# Model_64_Sequencer_Cartridge_v1.net
KiCad netlist of a schematic drawn in EAGLE
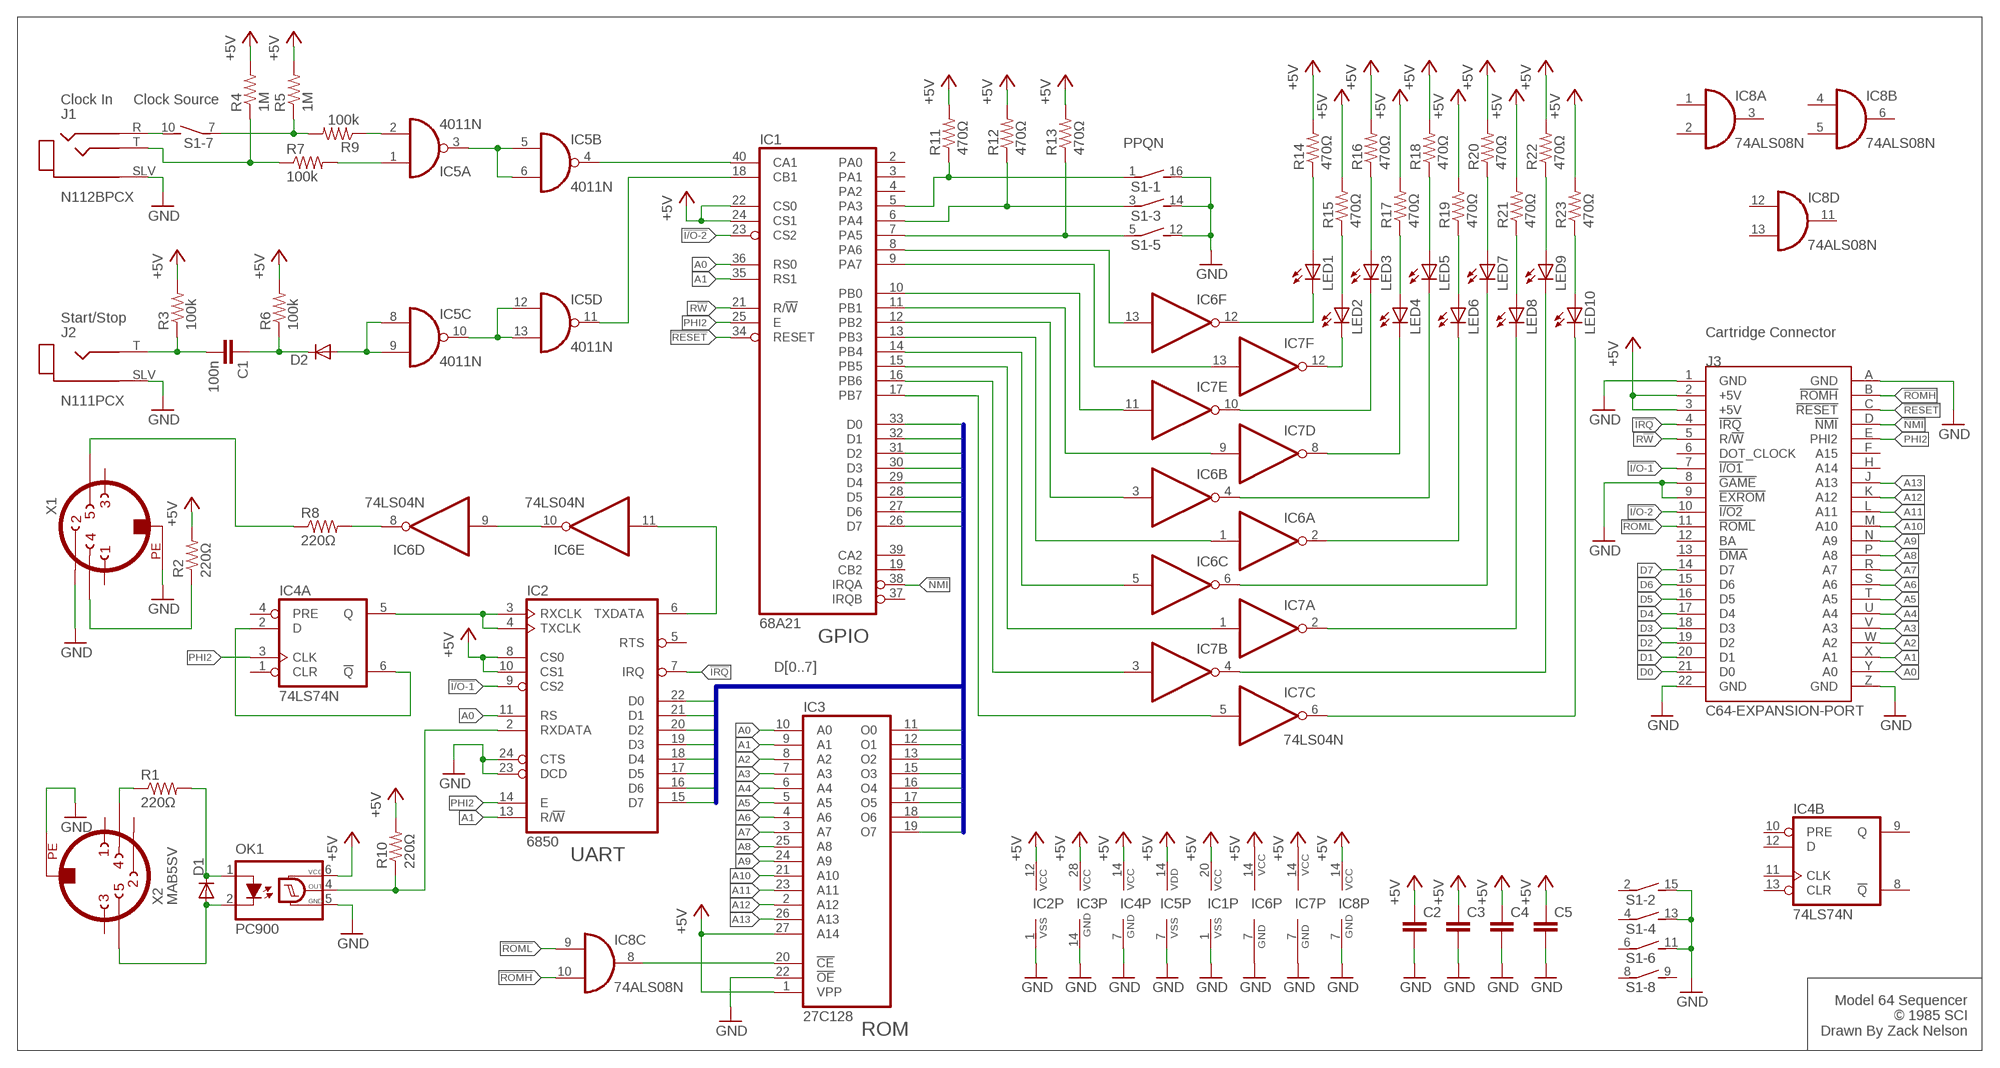
[diagram p0: schematic, sheet 1]

(export (version "E")
  (design (tool "Eeschema 10.0.6"))
  (components
    (comp (ref "C1")
      (value "100n")
      (footprint "eagle-import:C050-024X044")
      (libsource (lib "eagle-import") (part "C-EU050-024X044"))
    )
    (comp (ref "C2")
      (value "C-EU050-024X044")
      (footprint "eagle-import:C050-024X044")
      (libsource (lib "eagle-import") (part "C-EU050-024X044"))
    )
    (comp (ref "C3")
      (value "C-EU050-024X044")
      (footprint "eagle-import:C050-024X044")
      (libsource (lib "eagle-import") (part "C-EU050-024X044"))
    )
    (comp (ref "C4")
      (value "C-EU050-024X044")
      (footprint "eagle-import:C050-024X044")
      (libsource (lib "eagle-import") (part "C-EU050-024X044"))
    )
    (comp (ref "C5")
      (value "C-EU050-024X044")
      (footprint "eagle-import:C050-024X044")
      (libsource (lib "eagle-import") (part "C-EU050-024X044"))
    )
    (comp (ref "D1")
      (value "DIODE-D-7.5")
      (footprint "eagle-import:D-7.5")
      (libsource (lib "eagle-import") (part "DIODE-D-7.5"))
    )
    (comp (ref "D2")
      (value "DIODE-D-7.5")
      (footprint "eagle-import:D-7.5")
      (libsource (lib "eagle-import") (part "DIODE-D-7.5"))
    )
    (comp (ref "IC1")
      (value "68A21")
      (footprint "eagle-import:DIL40")
      (fields (field (name "MF") "NTE ELECTRONICS") (field (name "MPN") "NTE6821"))
      (libsource (lib "eagle-import") (part "6821"))
    )
    (comp (ref "IC2")
      (value "6850")
      (footprint "eagle-import:DIL24")
      (fields (field (name "MF") "NTE ELECTRONICS") (field (name "MPN") "NTE6850"))
      (libsource (lib "eagle-import") (part "6850"))
    )
    (comp (ref "IC3")
      (value "27C128")
      (footprint "eagle-import:DIL28")
      (libsource (lib "eagle-import") (part "27256"))
    )
    (comp (ref "IC4")
      (value "74LS74N")
      (footprint "eagle-import:DIL14")
      (libsource (lib "eagle-import") (part "7474NLS"))
    )
    (comp (ref "IC5")
      (value "4011N")
      (footprint "eagle-import:DIL14")
      (libsource (lib "eagle-import") (part "4011N"))
    )
    (comp (ref "IC6")
      (value "74LS04N")
      (footprint "eagle-import:DIL14")
      (libsource (lib "eagle-import") (part "7404NLS"))
    )
    (comp (ref "IC7")
      (value "74LS04N")
      (footprint "eagle-import:DIL14")
      (libsource (lib "eagle-import") (part "7404NLS"))
    )
    (comp (ref "IC8")
      (value "74ALS08N")
      (footprint "eagle-import:DIL14")
      (libsource (lib "eagle-import") (part "7408NALS"))
    )
    (comp (ref "J1")
      (value "N112BPCX")
      (footprint "eagle-import:SWITCHCRAFT_N112BPCX")
      (fields (field (name "MANUFACTURER") "Switchcarft"))
      (libsource (lib "eagle-import") (part "N112BPCX"))
    )
    (comp (ref "J2")
      (value "N111PCX")
      (footprint "eagle-import:SWITCHCRAFT_N111PCX")
      (fields (field (name "MANUFACTURER") "Switchcarft"))
      (libsource (lib "eagle-import") (part "N111PCX"))
    )
    (comp (ref "J3")
      (value "C64-EXPANSION-PORT")
      (footprint "eagle-import:EXPANSIO_SQ")
      (libsource (lib "eagle-import") (part "C64-EXPANSIONPNARROW"))
    )
    (comp (ref "LED1")
      (value "LED3MM")
      (footprint "eagle-import:LED3MM")
      (libsource (lib "eagle-import") (part "LED3MM"))
    )
    (comp (ref "LED2")
      (value "LED3MM")
      (footprint "eagle-import:LED3MM")
      (libsource (lib "eagle-import") (part "LED3MM"))
    )
    (comp (ref "LED3")
      (value "LED3MM")
      (footprint "eagle-import:LED3MM")
      (libsource (lib "eagle-import") (part "LED3MM"))
    )
    (comp (ref "LED4")
      (value "LED3MM")
      (footprint "eagle-import:LED3MM")
      (libsource (lib "eagle-import") (part "LED3MM"))
    )
    (comp (ref "LED5")
      (value "LED3MM")
      (footprint "eagle-import:LED3MM")
      (libsource (lib "eagle-import") (part "LED3MM"))
    )
    (comp (ref "LED6")
      (value "LED3MM")
      (footprint "eagle-import:LED3MM")
      (libsource (lib "eagle-import") (part "LED3MM"))
    )
    (comp (ref "LED7")
      (value "LED3MM")
      (footprint "eagle-import:LED3MM")
      (libsource (lib "eagle-import") (part "LED3MM"))
    )
    (comp (ref "LED8")
      (value "LED3MM")
      (footprint "eagle-import:LED3MM")
      (libsource (lib "eagle-import") (part "LED3MM"))
    )
    (comp (ref "LED9")
      (value "LED3MM")
      (footprint "eagle-import:LED3MM")
      (libsource (lib "eagle-import") (part "LED3MM"))
    )
    (comp (ref "LED10")
      (value "LED3MM")
      (footprint "eagle-import:LED3MM")
      (libsource (lib "eagle-import") (part "LED3MM"))
    )
    (comp (ref "OK1")
      (value "PC900")
      (footprint "eagle-import:DIL06")
      (fields (field (name "MF") "FAIRCHILD SEMICONDUCTOR") (field (name "MPN") "H11L1-M"))
      (libsource (lib "eagle-import") (part "H11LM1"))
    )
    (comp (ref "R1")
      (value "220Ω")
      (footprint "eagle-import:0207_12")
      (libsource (lib "eagle-import") (part "R-US_0207/12"))
    )
    (comp (ref "R2")
      (value "220Ω")
      (footprint "eagle-import:0207_12")
      (libsource (lib "eagle-import") (part "R-US_0207/12"))
    )
    (comp (ref "R3")
      (value "100k")
      (footprint "eagle-import:0207_12")
      (libsource (lib "eagle-import") (part "R-US_0207/12"))
    )
    (comp (ref "R4")
      (value "1M")
      (footprint "eagle-import:0207_12")
      (libsource (lib "eagle-import") (part "R-US_0207/12"))
    )
    (comp (ref "R5")
      (value "1M")
      (footprint "eagle-import:0207_12")
      (libsource (lib "eagle-import") (part "R-US_0207/12"))
    )
    (comp (ref "R6")
      (value "100k")
      (footprint "eagle-import:0207_12")
      (libsource (lib "eagle-import") (part "R-US_0207/12"))
    )
    (comp (ref "R7")
      (value "100k")
      (footprint "eagle-import:0207_12")
      (libsource (lib "eagle-import") (part "R-US_0207/12"))
    )
    (comp (ref "R8")
      (value "220Ω")
      (footprint "eagle-import:0207_12")
      (libsource (lib "eagle-import") (part "R-US_0207/12"))
    )
    (comp (ref "R9")
      (value "100k")
      (footprint "eagle-import:0207_12")
      (libsource (lib "eagle-import") (part "R-US_0207/12"))
    )
    (comp (ref "R10")
      (value "220Ω")
      (footprint "eagle-import:0207_12")
      (libsource (lib "eagle-import") (part "R-US_0207/12"))
    )
    (comp (ref "R11")
      (value "470Ω")
      (footprint "eagle-import:0207_12")
      (libsource (lib "eagle-import") (part "R-US_0207/12"))
    )
    (comp (ref "R12")
      (value "470Ω")
      (footprint "eagle-import:0207_12")
      (libsource (lib "eagle-import") (part "R-US_0207/12"))
    )
    (comp (ref "R13")
      (value "470Ω")
      (footprint "eagle-import:0207_12")
      (libsource (lib "eagle-import") (part "R-US_0207/12"))
    )
    (comp (ref "R14")
      (value "470Ω")
      (footprint "eagle-import:0207_12")
      (libsource (lib "eagle-import") (part "R-US_0207/12"))
    )
    (comp (ref "R15")
      (value "470Ω")
      (footprint "eagle-import:0207_12")
      (libsource (lib "eagle-import") (part "R-US_0207/12"))
    )
    (comp (ref "R16")
      (value "470Ω")
      (footprint "eagle-import:0207_12")
      (libsource (lib "eagle-import") (part "R-US_0207/12"))
    )
    (comp (ref "R17")
      (value "470Ω")
      (footprint "eagle-import:0207_12")
      (libsource (lib "eagle-import") (part "R-US_0207/12"))
    )
    (comp (ref "R18")
      (value "470Ω")
      (footprint "eagle-import:0207_12")
      (libsource (lib "eagle-import") (part "R-US_0207/12"))
    )
    (comp (ref "R19")
      (value "470Ω")
      (footprint "eagle-import:0207_12")
      (libsource (lib "eagle-import") (part "R-US_0207/12"))
    )
    (comp (ref "R20")
      (value "470Ω")
      (footprint "eagle-import:0207_12")
      (libsource (lib "eagle-import") (part "R-US_0207/12"))
    )
    (comp (ref "R21")
      (value "470Ω")
      (footprint "eagle-import:0207_12")
      (libsource (lib "eagle-import") (part "R-US_0207/12"))
    )
    (comp (ref "R22")
      (value "470Ω")
      (footprint "eagle-import:0207_12")
      (libsource (lib "eagle-import") (part "R-US_0207/12"))
    )
    (comp (ref "R23")
      (value "470Ω")
      (footprint "eagle-import:0207_12")
      (libsource (lib "eagle-import") (part "R-US_0207/12"))
    )
    (comp (ref "S1")
      (value "DIP08S")
      (footprint "eagle-import:DIP08S")
      (libsource (lib "eagle-import") (part "DIP08S"))
    )
    (comp (ref "X1")
      (value "MAB5SV")
      (footprint "eagle-import:MAB5SV")
      (libsource (lib "eagle-import") (part "MAB5SV"))
    )
    (comp (ref "X2")
      (value "MAB5SV")
      (footprint "eagle-import:MAB5SV")
      (libsource (lib "eagle-import") (part "MAB5SV"))
    )
  )
  (nets
    (net (code "1") (name "+5V") (class "Default")
      (node (ref "C2") (pin "1") (pinfunction "1_1") (pintype "passive"))
      (node (ref "C3") (pin "1") (pinfunction "1_1") (pintype "passive"))
      (node (ref "C4") (pin "1") (pinfunction "1_1") (pintype "passive"))
      (node (ref "C5") (pin "1") (pinfunction "1_1") (pintype "passive"))
      (node (ref "IC1") (pin "20") (pinfunction "VCC_20") (pintype "power_in"))
      (node (ref "IC1") (pin "22") (pinfunction "CS0_22") (pintype "input"))
      (node (ref "IC1") (pin "24") (pinfunction "CS1_24") (pintype "input"))
      (node (ref "IC2") (pin "10") (pinfunction "CS1_10") (pintype "input"))
      (node (ref "IC2") (pin "12") (pinfunction "VCC_12") (pintype "power_in"))
      (node (ref "IC2") (pin "8") (pinfunction "CS0_8") (pintype "input"))
      (node (ref "IC3") (pin "1") (pinfunction "VPP_1") (pintype "input"))
      (node (ref "IC3") (pin "27") (pinfunction "A14_27") (pintype "input"))
      (node (ref "IC3") (pin "28") (pinfunction "VCC_28") (pintype "power_in"))
      (node (ref "IC4") (pin "14") (pinfunction "VCC_14") (pintype "power_in"))
      (node (ref "IC5") (pin "14") (pinfunction "VDD_14") (pintype "power_in"))
      (node (ref "IC6") (pin "14") (pinfunction "VCC_14") (pintype "power_in"))
      (node (ref "IC7") (pin "14") (pinfunction "VCC_14") (pintype "power_in"))
      (node (ref "IC8") (pin "14") (pinfunction "VCC_14") (pintype "power_in"))
      (node (ref "J3") (pin "2") (pinfunction "+5V_2") (pintype "power_in"))
      (node (ref "J3") (pin "3") (pinfunction "+5V_3") (pintype "power_in"))
      (node (ref "OK1") (pin "6") (pinfunction "VCC_6") (pintype "power_in"))
      (node (ref "R10") (pin "2") (pinfunction "2_2") (pintype "passive"))
      (node (ref "R11") (pin "2") (pinfunction "2_2") (pintype "passive"))
      (node (ref "R12") (pin "2") (pinfunction "2_2") (pintype "passive"))
      (node (ref "R13") (pin "2") (pinfunction "2_2") (pintype "passive"))
      (node (ref "R14") (pin "2") (pinfunction "2_2") (pintype "passive"))
      (node (ref "R15") (pin "2") (pinfunction "2_2") (pintype "passive"))
      (node (ref "R16") (pin "2") (pinfunction "2_2") (pintype "passive"))
      (node (ref "R17") (pin "2") (pinfunction "2_2") (pintype "passive"))
      (node (ref "R18") (pin "2") (pinfunction "2_2") (pintype "passive"))
      (node (ref "R19") (pin "2") (pinfunction "2_2") (pintype "passive"))
      (node (ref "R2") (pin "2") (pinfunction "2_2") (pintype "passive"))
      (node (ref "R20") (pin "2") (pinfunction "2_2") (pintype "passive"))
      (node (ref "R21") (pin "2") (pinfunction "2_2") (pintype "passive"))
      (node (ref "R22") (pin "2") (pinfunction "2_2") (pintype "passive"))
      (node (ref "R23") (pin "2") (pinfunction "2_2") (pintype "passive"))
      (node (ref "R3") (pin "2") (pinfunction "2_2") (pintype "passive"))
      (node (ref "R4") (pin "2") (pinfunction "2_2") (pintype "passive"))
      (node (ref "R5") (pin "2") (pinfunction "2_2") (pintype "passive"))
      (node (ref "R6") (pin "2") (pinfunction "2_2") (pintype "passive"))
    )
    (net (code "3") (name "/R~{W}") (class "Default")
      (node (ref "IC1") (pin "21") (pinfunction "R/~{W}_21") (pintype "input"))
      (node (ref "J3") (pin "5") (pinfunction "R/~{W}_5") (pintype "output"))
    )
    (net (code "4") (name "/~{IRQ}") (class "Default")
      (node (ref "IC2") (pin "7") (pinfunction "IRQ_7") (pintype "output"))
      (node (ref "J3") (pin "4") (pinfunction "~{IRQ}_4") (pintype "input"))
    )
    (net (code "5") (name "/~{I{slash}O-1}") (class "Default")
      (node (ref "IC2") (pin "9") (pinfunction "CS2_9") (pintype "input"))
      (node (ref "J3") (pin "7") (pinfunction "~{I/O1}_7") (pintype "output"))
    )
    (net (code "6") (name "/~{I{slash}O-2}") (class "Default")
      (node (ref "IC1") (pin "23") (pinfunction "CS2_23") (pintype "input"))
      (node (ref "J3") (pin "10") (pinfunction "~{I/O2}_10") (pintype "output"))
    )
    (net (code "7") (name "/~{NMI}") (class "Default")
      (node (ref "IC1") (pin "38") (pinfunction "IRQA_38") (pintype "open_collector"))
      (node (ref "J3") (pin "D") (pinfunction "~{NMI}_D") (pintype "input"))
    )
    (net (code "8") (name "/~{RESET}") (class "Default")
      (node (ref "IC1") (pin "34") (pinfunction "RESET_34") (pintype "input"))
      (node (ref "J3") (pin "C") (pinfunction "~{RESET}_C") (pintype "open_collector"))
    )
    (net (code "9") (name "/~{ROMH}") (class "Default")
      (node (ref "IC8") (pin "10") (pinfunction "I1_10") (pintype "input"))
      (node (ref "J3") (pin "B") (pinfunction "~{ROMH}_B") (pintype "output"))
    )
    (net (code "10") (name "/~{ROML}") (class "Default")
      (node (ref "IC8") (pin "9") (pinfunction "I0_9") (pintype "input"))
      (node (ref "J3") (pin "11") (pinfunction "~{ROML}_11") (pintype "output"))
    )
    (net (code "11") (name "A0") (class "Default")
      (node (ref "IC1") (pin "36") (pinfunction "RS0_36") (pintype "input"))
      (node (ref "IC2") (pin "11") (pinfunction "RS_11") (pintype "input"))
      (node (ref "IC3") (pin "10") (pinfunction "A0_10") (pintype "input"))
      (node (ref "J3") (pin "Y") (pinfunction "A0_Y") (pintype "bidirectional"))
    )
    (net (code "12") (name "A1") (class "Default")
      (node (ref "IC1") (pin "35") (pinfunction "RS1_35") (pintype "input"))
      (node (ref "IC2") (pin "13") (pinfunction "R/~{W}_13") (pintype "input"))
      (node (ref "IC3") (pin "9") (pinfunction "A1_9") (pintype "input"))
      (node (ref "J3") (pin "X") (pinfunction "A1_X") (pintype "bidirectional"))
    )
    (net (code "13") (name "A2") (class "Default")
      (node (ref "IC3") (pin "8") (pinfunction "A2_8") (pintype "input"))
      (node (ref "J3") (pin "W") (pinfunction "A2_W") (pintype "bidirectional"))
    )
    (net (code "14") (name "A3") (class "Default")
      (node (ref "IC3") (pin "7") (pinfunction "A3_7") (pintype "input"))
      (node (ref "J3") (pin "V") (pinfunction "A3_V") (pintype "bidirectional"))
    )
    (net (code "15") (name "A4") (class "Default")
      (node (ref "IC3") (pin "6") (pinfunction "A4_6") (pintype "input"))
      (node (ref "J3") (pin "U") (pinfunction "A4_U") (pintype "bidirectional"))
    )
    (net (code "16") (name "A5") (class "Default")
      (node (ref "IC3") (pin "5") (pinfunction "A5_5") (pintype "input"))
      (node (ref "J3") (pin "T") (pinfunction "A5_T") (pintype "bidirectional"))
    )
    (net (code "17") (name "A6") (class "Default")
      (node (ref "IC3") (pin "4") (pinfunction "A6_4") (pintype "input"))
      (node (ref "J3") (pin "S") (pinfunction "A6_S") (pintype "bidirectional"))
    )
    (net (code "18") (name "A7") (class "Default")
      (node (ref "IC3") (pin "3") (pinfunction "A7_3") (pintype "input"))
      (node (ref "J3") (pin "R") (pinfunction "A7_R") (pintype "bidirectional"))
    )
    (net (code "19") (name "A8") (class "Default")
      (node (ref "IC3") (pin "25") (pinfunction "A8_25") (pintype "input"))
      (node (ref "J3") (pin "P") (pinfunction "A8_P") (pintype "bidirectional"))
    )
    (net (code "20") (name "A9") (class "Default")
      (node (ref "IC3") (pin "24") (pinfunction "A9_24") (pintype "input"))
      (node (ref "J3") (pin "N") (pinfunction "A9_N") (pintype "bidirectional"))
    )
    (net (code "21") (name "A10") (class "Default")
      (node (ref "IC3") (pin "21") (pinfunction "A10_21") (pintype "input"))
      (node (ref "J3") (pin "M") (pinfunction "A10_M") (pintype "bidirectional"))
    )
    (net (code "22") (name "A11") (class "Default")
      (node (ref "IC3") (pin "23") (pinfunction "A11_23") (pintype "input"))
      (node (ref "J3") (pin "L") (pinfunction "A11_L") (pintype "bidirectional"))
    )
    (net (code "23") (name "A12") (class "Default")
      (node (ref "IC3") (pin "2") (pinfunction "A12_2") (pintype "input"))
      (node (ref "J3") (pin "K") (pinfunction "A12_K") (pintype "bidirectional"))
    )
    (net (code "24") (name "A13") (class "Default")
      (node (ref "IC3") (pin "26") (pinfunction "A13_26") (pintype "input"))
      (node (ref "J3") (pin "J") (pinfunction "A13_J") (pintype "bidirectional"))
    )
    (net (code "25") (name "D0") (class "Default")
      (node (ref "IC1") (pin "33") (pinfunction "D0_33") (pintype "bidirectional"))
      (node (ref "IC2") (pin "22") (pinfunction "D0_22") (pintype "bidirectional"))
      (node (ref "IC3") (pin "11") (pinfunction "O0_11") (pintype "tri_state"))
      (node (ref "J3") (pin "21") (pinfunction "D0_21") (pintype "bidirectional"))
    )
    (net (code "26") (name "D1") (class "Default")
      (node (ref "IC1") (pin "32") (pinfunction "D1_32") (pintype "bidirectional"))
      (node (ref "IC2") (pin "21") (pinfunction "D1_21") (pintype "bidirectional"))
      (node (ref "IC3") (pin "12") (pinfunction "O1_12") (pintype "tri_state"))
      (node (ref "J3") (pin "20") (pinfunction "D1_20") (pintype "bidirectional"))
    )
    (net (code "27") (name "D2") (class "Default")
      (node (ref "IC1") (pin "31") (pinfunction "D2_31") (pintype "bidirectional"))
      (node (ref "IC2") (pin "20") (pinfunction "D2_20") (pintype "bidirectional"))
      (node (ref "IC3") (pin "13") (pinfunction "O2_13") (pintype "tri_state"))
      (node (ref "J3") (pin "19") (pinfunction "D2_19") (pintype "bidirectional"))
    )
    (net (code "28") (name "D3") (class "Default")
      (node (ref "IC1") (pin "30") (pinfunction "D3_30") (pintype "bidirectional"))
      (node (ref "IC2") (pin "19") (pinfunction "D3_19") (pintype "bidirectional"))
      (node (ref "IC3") (pin "15") (pinfunction "O3_15") (pintype "tri_state"))
      (node (ref "J3") (pin "18") (pinfunction "D3_18") (pintype "bidirectional"))
    )
    (net (code "29") (name "D4") (class "Default")
      (node (ref "IC1") (pin "29") (pinfunction "D4_29") (pintype "bidirectional"))
      (node (ref "IC2") (pin "18") (pinfunction "D4_18") (pintype "bidirectional"))
      (node (ref "IC3") (pin "16") (pinfunction "O4_16") (pintype "tri_state"))
      (node (ref "J3") (pin "17") (pinfunction "D4_17") (pintype "bidirectional"))
    )
    (net (code "30") (name "D5") (class "Default")
      (node (ref "IC1") (pin "28") (pinfunction "D5_28") (pintype "bidirectional"))
      (node (ref "IC2") (pin "17") (pinfunction "D5_17") (pintype "bidirectional"))
      (node (ref "IC3") (pin "17") (pinfunction "O5_17") (pintype "tri_state"))
      (node (ref "J3") (pin "16") (pinfunction "D5_16") (pintype "bidirectional"))
    )
    (net (code "31") (name "D6") (class "Default")
      (node (ref "IC1") (pin "27") (pinfunction "D6_27") (pintype "bidirectional"))
      (node (ref "IC2") (pin "16") (pinfunction "D6_16") (pintype "bidirectional"))
      (node (ref "IC3") (pin "18") (pinfunction "O6_18") (pintype "tri_state"))
      (node (ref "J3") (pin "15") (pinfunction "D6_15") (pintype "bidirectional"))
    )
    (net (code "32") (name "D7") (class "Default")
      (node (ref "IC1") (pin "26") (pinfunction "D7_26") (pintype "bidirectional"))
      (node (ref "IC2") (pin "15") (pinfunction "D7_15") (pintype "bidirectional"))
      (node (ref "IC3") (pin "19") (pinfunction "O7_19") (pintype "tri_state"))
      (node (ref "J3") (pin "14") (pinfunction "D7_14") (pintype "bidirectional"))
    )
    (net (code "33") (name "GND") (class "Default")
      (node (ref "C2") (pin "2") (pinfunction "2_2") (pintype "passive"))
      (node (ref "C3") (pin "2") (pinfunction "2_2") (pintype "passive"))
      (node (ref "C4") (pin "2") (pinfunction "2_2") (pintype "passive"))
      (node (ref "C5") (pin "2") (pinfunction "2_2") (pintype "passive"))
      (node (ref "IC1") (pin "1") (pinfunction "VSS_1") (pintype "power_in"))
      (node (ref "IC2") (pin "1") (pinfunction "VSS_1") (pintype "power_in"))
      (node (ref "IC2") (pin "23") (pinfunction "DCD_23") (pintype "input"))
      (node (ref "IC2") (pin "24") (pinfunction "CTS_24") (pintype "input"))
      (node (ref "IC3") (pin "14") (pinfunction "GND_14") (pintype "power_in"))
      (node (ref "IC3") (pin "22") (pinfunction "~{OE}_22") (pintype "input"))
      (node (ref "IC4") (pin "7") (pinfunction "GND_7") (pintype "power_in"))
      (node (ref "IC5") (pin "7") (pinfunction "VSS_7") (pintype "power_in"))
      (node (ref "IC6") (pin "7") (pinfunction "GND_7") (pintype "power_in"))
      (node (ref "IC7") (pin "7") (pinfunction "GND_7") (pintype "power_in"))
      (node (ref "IC8") (pin "7") (pinfunction "GND_7") (pintype "power_in"))
      (node (ref "J1") (pin "SLV") (pinfunction "SLEEVE_SLV") (pintype "passive"))
      (node (ref "J2") (pin "SLV") (pinfunction "SLEEVE_SLV") (pintype "passive"))
      (node (ref "J3") (pin "1") (pinfunction "GND_1") (pintype "power_in"))
      (node (ref "J3") (pin "22") (pinfunction "GND_22") (pintype "power_in"))
      (node (ref "J3") (pin "8") (pinfunction "~{GAME}_8") (pintype "input"))
      (node (ref "J3") (pin "9") (pinfunction "~{EXROM}_9") (pintype "input"))
      (node (ref "J3") (pin "A") (pinfunction "GND_A") (pintype "power_in"))
      (node (ref "J3") (pin "Z") (pinfunction "GND_Z") (pintype "power_in"))
      (node (ref "OK1") (pin "5") (pinfunction "GND_5") (pintype "power_in"))
      (node (ref "S1") (pin "11") (pinfunction "2_11") (pintype "passive"))
      (node (ref "S1") (pin "12") (pinfunction "2_12") (pintype "passive"))
      (node (ref "S1") (pin "13") (pinfunction "2_13") (pintype "passive"))
      (node (ref "S1") (pin "14") (pinfunction "2_14") (pintype "passive"))
      (node (ref "S1") (pin "15") (pinfunction "2_15") (pintype "passive"))
      (node (ref "S1") (pin "16") (pinfunction "2_16") (pintype "passive"))
      (node (ref "X1") (pin "2") (pinfunction "2_2") (pintype "passive"))
      (node (ref "X1") (pin "PE") (pinfunction "PE_PE") (pintype "power_in"))
      (node (ref "X2") (pin "PE") (pinfunction "PE_PE") (pintype "power_in"))
    )
    (net (code "34") (name "Net-(C1-Pad1)") (class "Default")
      (node (ref "C1") (pin "1") (pinfunction "1_1") (pintype "passive"))
      (node (ref "D2") (pin "C") (pinfunction "C_C") (pintype "passive"))
      (node (ref "R6") (pin "1") (pinfunction "1_1") (pintype "passive"))
    )
    (net (code "35") (name "Net-(IC1A-CA1)") (class "Default")
      (node (ref "IC1") (pin "40") (pinfunction "CA1_40") (pintype "input"))
      (node (ref "IC5") (pin "4") (pinfunction "O_4") (pintype "output"))
    )
    (net (code "36") (name "Net-(IC1A-CB1)") (class "Default")
      (node (ref "IC1") (pin "18") (pinfunction "CB1_18") (pintype "input"))
      (node (ref "IC5") (pin "11") (pinfunction "O_11") (pintype "output"))
    )
    (net (code "37") (name "Net-(IC1A-PA3)") (class "Default")
      (node (ref "IC1") (pin "5") (pinfunction "PA3_5") (pintype "bidirectional"))
      (node (ref "R11") (pin "1") (pinfunction "1_1") (pintype "passive"))
      (node (ref "S1") (pin "1") (pinfunction "1_1") (pintype "passive"))
    )
    (net (code "38") (name "Net-(IC1A-PA4)") (class "Default")
      (node (ref "IC1") (pin "6") (pinfunction "PA4_6") (pintype "bidirectional"))
      (node (ref "R12") (pin "1") (pinfunction "1_1") (pintype "passive"))
      (node (ref "S1") (pin "3") (pinfunction "1_3") (pintype "passive"))
    )
    (net (code "39") (name "Net-(IC1A-PA5)") (class "Default")
      (node (ref "IC1") (pin "7") (pinfunction "PA5_7") (pintype "bidirectional"))
      (node (ref "R13") (pin "1") (pinfunction "1_1") (pintype "passive"))
      (node (ref "S1") (pin "5") (pinfunction "1_5") (pintype "passive"))
    )
    (net (code "40") (name "Net-(IC1A-PA6)") (class "Default")
      (node (ref "IC1") (pin "8") (pinfunction "PA6_8") (pintype "bidirectional"))
      (node (ref "IC6") (pin "13") (pinfunction "I_13") (pintype "input"))
    )
    (net (code "41") (name "Net-(IC1A-PA7)") (class "Default")
      (node (ref "IC1") (pin "9") (pinfunction "PA7_9") (pintype "bidirectional"))
      (node (ref "IC7") (pin "13") (pinfunction "I_13") (pintype "input"))
    )
    (net (code "42") (name "Net-(IC1A-PB0)") (class "Default")
      (node (ref "IC1") (pin "10") (pinfunction "PB0_10") (pintype "bidirectional"))
      (node (ref "IC7") (pin "11") (pinfunction "I_11") (pintype "input"))
    )
    (net (code "43") (name "Net-(IC1A-PB1)") (class "Default")
      (node (ref "IC1") (pin "11") (pinfunction "PB1_11") (pintype "bidirectional"))
      (node (ref "IC7") (pin "9") (pinfunction "I_9") (pintype "input"))
    )
    (net (code "44") (name "Net-(IC1A-PB2)") (class "Default")
      (node (ref "IC1") (pin "12") (pinfunction "PB2_12") (pintype "bidirectional"))
      (node (ref "IC6") (pin "3") (pinfunction "I_3") (pintype "input"))
    )
    (net (code "45") (name "Net-(IC1A-PB3)") (class "Default")
      (node (ref "IC1") (pin "13") (pinfunction "PB3_13") (pintype "bidirectional"))
      (node (ref "IC6") (pin "1") (pinfunction "I_1") (pintype "input"))
    )
    (net (code "46") (name "Net-(IC1A-PB4)") (class "Default")
      (node (ref "IC1") (pin "14") (pinfunction "PB4_14") (pintype "bidirectional"))
      (node (ref "IC6") (pin "5") (pinfunction "I_5") (pintype "input"))
    )
    (net (code "47") (name "Net-(IC1A-PB5)") (class "Default")
      (node (ref "IC1") (pin "15") (pinfunction "PB5_15") (pintype "bidirectional"))
      (node (ref "IC7") (pin "1") (pinfunction "I_1") (pintype "input"))
    )
    (net (code "48") (name "Net-(IC1A-PB6)") (class "Default")
      (node (ref "IC1") (pin "16") (pinfunction "PB6_16") (pintype "bidirectional"))
      (node (ref "IC7") (pin "3") (pinfunction "I_3") (pintype "input"))
    )
    (net (code "49") (name "Net-(IC1A-PB7)") (class "Default")
      (node (ref "IC1") (pin "17") (pinfunction "PB7_17") (pintype "bidirectional"))
      (node (ref "IC7") (pin "5") (pinfunction "I_5") (pintype "input"))
    )
    (net (code "50") (name "Net-(IC2A-RXCLK)") (class "Default")
      (node (ref "IC2") (pin "3") (pinfunction "RXCLK_3") (pintype "input"))
      (node (ref "IC2") (pin "4") (pinfunction "TXCLK_4") (pintype "input"))
      (node (ref "IC4") (pin "5") (pinfunction "Q_5") (pintype "output"))
    )
    (net (code "51") (name "Net-(IC2A-RXDATA)") (class "Default")
      (node (ref "IC2") (pin "2") (pinfunction "RXDATA_2") (pintype "input"))
      (node (ref "OK1") (pin "4") (pinfunction "OUT_4") (pintype "output"))
      (node (ref "R10") (pin "1") (pinfunction "1_1") (pintype "passive"))
    )
    (net (code "52") (name "Net-(IC2A-TXDATA)") (class "Default")
      (node (ref "IC2") (pin "6") (pinfunction "TXDATA_6") (pintype "output"))
      (node (ref "IC6") (pin "11") (pinfunction "I_11") (pintype "input"))
    )
    (net (code "53") (name "Net-(IC3A-~{CE})") (class "Default")
      (node (ref "IC3") (pin "20") (pinfunction "~{CE}_20") (pintype "input"))
      (node (ref "IC8") (pin "8") (pinfunction "O_8") (pintype "output"))
    )
    (net (code "54") (name "Net-(IC4A-D)") (class "Default")
      (node (ref "IC4") (pin "2") (pinfunction "D_2") (pintype "input"))
      (node (ref "IC4") (pin "6") (pinfunction "~{Q}_6") (pintype "output"))
    )
    (net (code "55") (name "Net-(IC5A-I0)") (class "Default")
      (node (ref "IC5") (pin "1") (pinfunction "I0_1") (pintype "input"))
      (node (ref "R7") (pin "2") (pinfunction "2_2") (pintype "passive"))
    )
    (net (code "56") (name "Net-(IC5A-I1)") (class "Default")
      (node (ref "IC5") (pin "2") (pinfunction "I1_2") (pintype "input"))
      (node (ref "R9") (pin "1") (pinfunction "1_1") (pintype "passive"))
    )
    (net (code "57") (name "Net-(IC5A-O)") (class "Default")
      (node (ref "IC5") (pin "3") (pinfunction "O_3") (pintype "output"))
      (node (ref "IC5") (pin "5") (pinfunction "I0_5") (pintype "input"))
      (node (ref "IC5") (pin "6") (pinfunction "I1_6") (pintype "input"))
    )
    (net (code "58") (name "Net-(IC5C-I0)") (class "Default")
      (node (ref "D2") (pin "A") (pinfunction "A_A") (pintype "passive"))
      (node (ref "IC5") (pin "8") (pinfunction "I0_8") (pintype "input"))
      (node (ref "IC5") (pin "9") (pinfunction "I1_9") (pintype "input"))
    )
    (net (code "59") (name "Net-(IC5C-O)") (class "Default")
      (node (ref "IC5") (pin "10") (pinfunction "O_10") (pintype "output"))
      (node (ref "IC5") (pin "12") (pinfunction "I0_12") (pintype "input"))
      (node (ref "IC5") (pin "13") (pinfunction "I1_13") (pintype "input"))
    )
    (net (code "60") (name "Net-(IC6A-O)") (class "Default")
      (node (ref "IC6") (pin "2") (pinfunction "O_2") (pintype "output"))
      (node (ref "LED6") (pin "K") (pinfunction "C_K") (pintype "passive"))
    )
    (net (code "61") (name "Net-(IC6B-O)") (class "Default")
      (node (ref "IC6") (pin "4") (pinfunction "O_4") (pintype "output"))
      (node (ref "LED5") (pin "K") (pinfunction "C_K") (pintype "passive"))
    )
    (net (code "62") (name "Net-(IC6C-O)") (class "Default")
      (node (ref "IC6") (pin "6") (pinfunction "O_6") (pintype "output"))
      (node (ref "LED7") (pin "K") (pinfunction "C_K") (pintype "passive"))
    )
    (net (code "63") (name "Net-(IC6D-I)") (class "Default")
      (node (ref "IC6") (pin "10") (pinfunction "O_10") (pintype "output"))
      (node (ref "IC6") (pin "9") (pinfunction "I_9") (pintype "input"))
    )
    (net (code "64") (name "Net-(IC6D-O)") (class "Default")
      (node (ref "IC6") (pin "8") (pinfunction "O_8") (pintype "output"))
      (node (ref "R8") (pin "2") (pinfunction "2_2") (pintype "passive"))
    )
    (net (code "65") (name "Net-(IC6F-O)") (class "Default")
      (node (ref "IC6") (pin "12") (pinfunction "O_12") (pintype "output"))
      (node (ref "LED1") (pin "K") (pinfunction "C_K") (pintype "passive"))
    )
    (net (code "66") (name "Net-(IC7A-O)") (class "Default")
      (node (ref "IC7") (pin "2") (pinfunction "O_2") (pintype "output"))
      (node (ref "LED8") (pin "K") (pinfunction "C_K") (pintype "passive"))
    )
    (net (code "67") (name "Net-(IC7B-O)") (class "Default")
      (node (ref "IC7") (pin "4") (pinfunction "O_4") (pintype "output"))
      (node (ref "LED9") (pin "K") (pinfunction "C_K") (pintype "passive"))
    )
    (net (code "68") (name "Net-(IC7C-O)") (class "Default")
      (node (ref "IC7") (pin "6") (pinfunction "O_6") (pintype "output"))
      (node (ref "LED10") (pin "K") (pinfunction "C_K") (pintype "passive"))
    )
    (net (code "69") (name "Net-(IC7D-O)") (class "Default")
      (node (ref "IC7") (pin "8") (pinfunction "O_8") (pintype "output"))
      (node (ref "LED4") (pin "K") (pinfunction "C_K") (pintype "passive"))
    )
    (net (code "70") (name "Net-(IC7E-O)") (class "Default")
      (node (ref "IC7") (pin "10") (pinfunction "O_10") (pintype "output"))
      (node (ref "LED3") (pin "K") (pinfunction "C_K") (pintype "passive"))
    )
    (net (code "71") (name "Net-(IC7F-O)") (class "Default")
      (node (ref "IC7") (pin "12") (pinfunction "O_12") (pintype "output"))
      (node (ref "LED2") (pin "K") (pinfunction "C_K") (pintype "passive"))
    )
    (net (code "72") (name "Net-(J1-RING)") (class "Default")
      (node (ref "J1") (pin "R") (pinfunction "RING_R") (pintype "passive"))
      (node (ref "S1") (pin "10") (pinfunction "2_10") (pintype "passive"))
    )
    (net (code "73") (name "Net-(J1-TIP)") (class "Default")
      (node (ref "J1") (pin "T") (pinfunction "TIP_T") (pintype "passive"))
      (node (ref "R4") (pin "1") (pinfunction "1_1") (pintype "passive"))
      (node (ref "R7") (pin "1") (pinfunction "1_1") (pintype "passive"))
    )
    (net (code "74") (name "Net-(J2-TIP)") (class "Default")
      (node (ref "C1") (pin "2") (pinfunction "2_2") (pintype "passive"))
      (node (ref "J2") (pin "T") (pinfunction "TIP_T") (pintype "passive"))
      (node (ref "R3") (pin "1") (pinfunction "1_1") (pintype "passive"))
    )
    (net (code "75") (name "Net-(LED1-PadA)") (class "Default")
      (node (ref "LED1") (pin "A") (pinfunction "A_A") (pintype "passive"))
      (node (ref "R14") (pin "1") (pinfunction "1_1") (pintype "passive"))
    )
    (net (code "76") (name "Net-(LED2-PadA)") (class "Default")
      (node (ref "LED2") (pin "A") (pinfunction "A_A") (pintype "passive"))
      (node (ref "R15") (pin "1") (pinfunction "1_1") (pintype "passive"))
    )
    (net (code "77") (name "Net-(LED3-PadA)") (class "Default")
      (node (ref "LED3") (pin "A") (pinfunction "A_A") (pintype "passive"))
      (node (ref "R16") (pin "1") (pinfunction "1_1") (pintype "passive"))
    )
    (net (code "78") (name "Net-(LED4-PadA)") (class "Default")
      (node (ref "LED4") (pin "A") (pinfunction "A_A") (pintype "passive"))
      (node (ref "R17") (pin "1") (pinfunction "1_1") (pintype "passive"))
    )
    (net (code "79") (name "Net-(LED5-PadA)") (class "Default")
      (node (ref "LED5") (pin "A") (pinfunction "A_A") (pintype "passive"))
      (node (ref "R18") (pin "1") (pinfunction "1_1") (pintype "passive"))
    )
    (net (code "80") (name "Net-(LED6-PadA)") (class "Default")
      (node (ref "LED6") (pin "A") (pinfunction "A_A") (pintype "passive"))
      (node (ref "R19") (pin "1") (pinfunction "1_1") (pintype "passive"))
    )
    (net (code "81") (name "Net-(LED7-PadA)") (class "Default")
      (node (ref "LED7") (pin "A") (pinfunction "A_A") (pintype "passive"))
      (node (ref "R20") (pin "1") (pinfunction "1_1") (pintype "passive"))
    )
    (net (code "82") (name "Net-(LED8-PadA)") (class "Default")
      (node (ref "LED8") (pin "A") (pinfunction "A_A") (pintype "passive"))
      (node (ref "R21") (pin "1") (pinfunction "1_1") (pintype "passive"))
    )
    (net (code "83") (name "Net-(LED9-PadA)") (class "Default")
      (node (ref "LED9") (pin "A") (pinfunction "A_A") (pintype "passive"))
      (node (ref "R22") (pin "1") (pinfunction "1_1") (pintype "passive"))
    )
    (net (code "84") (name "Net-(LED10-PadA)") (class "Default")
      (node (ref "LED10") (pin "A") (pinfunction "A_A") (pintype "passive"))
      (node (ref "R23") (pin "1") (pinfunction "1_1") (pintype "passive"))
    )
    (net (code "85") (name "Net-(OK1-A)") (class "Default")
      (node (ref "D1") (pin "C") (pinfunction "C_C") (pintype "passive"))
      (node (ref "OK1") (pin "1") (pinfunction "A_1") (pintype "passive"))
      (node (ref "R1") (pin "2") (pinfunction "2_2") (pintype "passive"))
    )
    (net (code "86") (name "Net-(OK1-C)") (class "Default")
      (node (ref "D1") (pin "A") (pinfunction "A_A") (pintype "passive"))
      (node (ref "OK1") (pin "2") (pinfunction "C_2") (pintype "passive"))
      (node (ref "X2") (pin "5") (pinfunction "5_5") (pintype "passive"))
    )
    (net (code "87") (name "Net-(R1-Pad1)") (class "Default")
      (node (ref "R1") (pin "1") (pinfunction "1_1") (pintype "passive"))
      (node (ref "X2") (pin "4") (pinfunction "4_4") (pintype "passive"))
    )
    (net (code "88") (name "Net-(R2-Pad1)") (class "Default")
      (node (ref "R2") (pin "1") (pinfunction "1_1") (pintype "passive"))
      (node (ref "X1") (pin "4") (pinfunction "4_4") (pintype "passive"))
    )
    (net (code "89") (name "Net-(R8-Pad1)") (class "Default")
      (node (ref "R8") (pin "1") (pinfunction "1_1") (pintype "passive"))
      (node (ref "X1") (pin "5") (pinfunction "5_5") (pintype "passive"))
    )
    (net (code "90") (name "Net-(S1G-1)") (class "Default")
      (node (ref "R5") (pin "1") (pinfunction "1_1") (pintype "passive"))
      (node (ref "R9") (pin "2") (pinfunction "2_2") (pintype "passive"))
      (node (ref "S1") (pin "7") (pinfunction "1_7") (pintype "passive"))
    )
    (net (code "91") (name "PHI2") (class "Default")
      (node (ref "IC1") (pin "25") (pinfunction "E_25") (pintype "input"))
      (node (ref "IC2") (pin "14") (pinfunction "E_14") (pintype "input"))
      (node (ref "IC4") (pin "3") (pinfunction "CLK_3") (pintype "input"))
      (node (ref "J3") (pin "E") (pinfunction "PHI2_E") (pintype "output"))
    )
    (net (code "92") (name "unconnected-(IC1A-CA2-Pad39)") (class "Default")
      (node (ref "IC1") (pin "39") (pinfunction "CA2_39") (pintype "bidirectional"))
    )
    (net (code "93") (name "unconnected-(IC1A-CB2-Pad19)") (class "Default")
      (node (ref "IC1") (pin "19") (pinfunction "CB2_19") (pintype "bidirectional"))
    )
    (net (code "94") (name "unconnected-(IC1A-IRQB-Pad37)") (class "Default")
      (node (ref "IC1") (pin "37") (pinfunction "IRQB_37") (pintype "open_collector"))
    )
    (net (code "95") (name "unconnected-(IC1A-PA0-Pad2)") (class "Default")
      (node (ref "IC1") (pin "2") (pinfunction "PA0_2") (pintype "bidirectional"))
    )
    (net (code "96") (name "unconnected-(IC1A-PA1-Pad3)") (class "Default")
      (node (ref "IC1") (pin "3") (pinfunction "PA1_3") (pintype "bidirectional"))
    )
    (net (code "97") (name "unconnected-(IC1A-PA2-Pad4)") (class "Default")
      (node (ref "IC1") (pin "4") (pinfunction "PA2_4") (pintype "bidirectional"))
    )
    (net (code "98") (name "unconnected-(IC2A-RTS-Pad5)") (class "Default")
      (node (ref "IC2") (pin "5") (pinfunction "RTS_5") (pintype "output"))
    )
    (net (code "99") (name "unconnected-(IC4A-CLR-Pad1)") (class "Default")
      (node (ref "IC4") (pin "1") (pinfunction "CLR_1") (pintype "input"))
    )
    (net (code "100") (name "unconnected-(IC4A-PRE-Pad4)") (class "Default")
      (node (ref "IC4") (pin "4") (pinfunction "PRE_4") (pintype "input"))
    )
    (net (code "101") (name "unconnected-(IC4B-CLK-Pad11)") (class "Default")
      (node (ref "IC4") (pin "11") (pinfunction "CLK_11") (pintype "input"))
    )
    (net (code "102") (name "unconnected-(IC4B-CLR-Pad13)") (class "Default")
      (node (ref "IC4") (pin "13") (pinfunction "CLR_13") (pintype "input"))
    )
    (net (code "103") (name "unconnected-(IC4B-D-Pad12)") (class "Default")
      (node (ref "IC4") (pin "12") (pinfunction "D_12") (pintype "input"))
    )
    (net (code "104") (name "unconnected-(IC4B-PRE-Pad10)") (class "Default")
      (node (ref "IC4") (pin "10") (pinfunction "PRE_10") (pintype "input"))
    )
    (net (code "105") (name "unconnected-(IC4B-Q-Pad9)") (class "Default")
      (node (ref "IC4") (pin "9") (pinfunction "Q_9") (pintype "output"))
    )
    (net (code "106") (name "unconnected-(IC4B-~{Q}-Pad8)") (class "Default")
      (node (ref "IC4") (pin "8") (pinfunction "~{Q}_8") (pintype "output"))
    )
    (net (code "107") (name "unconnected-(IC8A-I0-Pad1)") (class "Default")
      (node (ref "IC8") (pin "1") (pinfunction "I0_1") (pintype "input"))
    )
    (net (code "108") (name "unconnected-(IC8A-I1-Pad2)") (class "Default")
      (node (ref "IC8") (pin "2") (pinfunction "I1_2") (pintype "input"))
    )
    (net (code "109") (name "unconnected-(IC8A-O-Pad3)") (class "Default")
      (node (ref "IC8") (pin "3") (pinfunction "O_3") (pintype "output"))
    )
    (net (code "110") (name "unconnected-(IC8B-I0-Pad4)") (class "Default")
      (node (ref "IC8") (pin "4") (pinfunction "I0_4") (pintype "input"))
    )
    (net (code "111") (name "unconnected-(IC8B-I1-Pad5)") (class "Default")
      (node (ref "IC8") (pin "5") (pinfunction "I1_5") (pintype "input"))
    )
    (net (code "112") (name "unconnected-(IC8B-O-Pad6)") (class "Default")
      (node (ref "IC8") (pin "6") (pinfunction "O_6") (pintype "output"))
    )
    (net (code "113") (name "unconnected-(IC8D-I0-Pad12)") (class "Default")
      (node (ref "IC8") (pin "12") (pinfunction "I0_12") (pintype "input"))
    )
    (net (code "114") (name "unconnected-(IC8D-I1-Pad13)") (class "Default")
      (node (ref "IC8") (pin "13") (pinfunction "I1_13") (pintype "input"))
    )
    (net (code "115") (name "unconnected-(IC8D-O-Pad11)") (class "Default")
      (node (ref "IC8") (pin "11") (pinfunction "O_11") (pintype "output"))
    )
    (net (code "116") (name "unconnected-(J3-A14-PadH)") (class "Default")
      (node (ref "J3") (pin "H") (pinfunction "A14_H") (pintype "bidirectional"))
    )
    (net (code "117") (name "unconnected-(J3-A15-PadF)") (class "Default")
      (node (ref "J3") (pin "F") (pinfunction "A15_F") (pintype "bidirectional"))
    )
    (net (code "118") (name "unconnected-(J3-BA-Pad12)") (class "Default")
      (node (ref "J3") (pin "12") (pinfunction "BA_12") (pintype "output"))
    )
    (net (code "119") (name "unconnected-(J3-DOT_CLOCK-Pad6)") (class "Default")
      (node (ref "J3") (pin "6") (pinfunction "DOT_CLOCK_6") (pintype "output"))
    )
    (net (code "120") (name "unconnected-(J3-~{DMA}-Pad13)") (class "Default")
      (node (ref "J3") (pin "13") (pinfunction "~{DMA}_13") (pintype "input"))
    )
    (net (code "121") (name "unconnected-(S1B-1-Pad2)") (class "Default")
      (node (ref "S1") (pin "2") (pinfunction "1_2") (pintype "passive"))
    )
    (net (code "122") (name "unconnected-(S1D-1-Pad4)") (class "Default")
      (node (ref "S1") (pin "4") (pinfunction "1_4") (pintype "passive"))
    )
    (net (code "123") (name "unconnected-(S1F-1-Pad6)") (class "Default")
      (node (ref "S1") (pin "6") (pinfunction "1_6") (pintype "passive"))
    )
    (net (code "124") (name "unconnected-(S1H-1-Pad8)") (class "Default")
      (node (ref "S1") (pin "8") (pinfunction "1_8") (pintype "passive"))
    )
    (net (code "125") (name "unconnected-(S1H-2-Pad9)") (class "Default")
      (node (ref "S1") (pin "9") (pinfunction "2_9") (pintype "passive"))
    )
    (net (code "126") (name "unconnected-(X1-Pad1)") (class "Default")
      (node (ref "X1") (pin "1") (pinfunction "1_1") (pintype "passive"))
    )
    (net (code "127") (name "unconnected-(X1-Pad3)") (class "Default")
      (node (ref "X1") (pin "3") (pinfunction "3_3") (pintype "passive"))
    )
    (net (code "128") (name "unconnected-(X2-Pad1)") (class "Default")
      (node (ref "X2") (pin "1") (pinfunction "1_1") (pintype "passive"))
    )
    (net (code "129") (name "unconnected-(X2-Pad2)") (class "Default")
      (node (ref "X2") (pin "2") (pinfunction "2_2") (pintype "passive"))
    )
    (net (code "130") (name "unconnected-(X2-Pad3)") (class "Default")
      (node (ref "X2") (pin "3") (pinfunction "3_3") (pintype "passive"))
    )
  )
)
